# first_node_v2.net
KiCad netlist of a schematic drawn in EAGLE
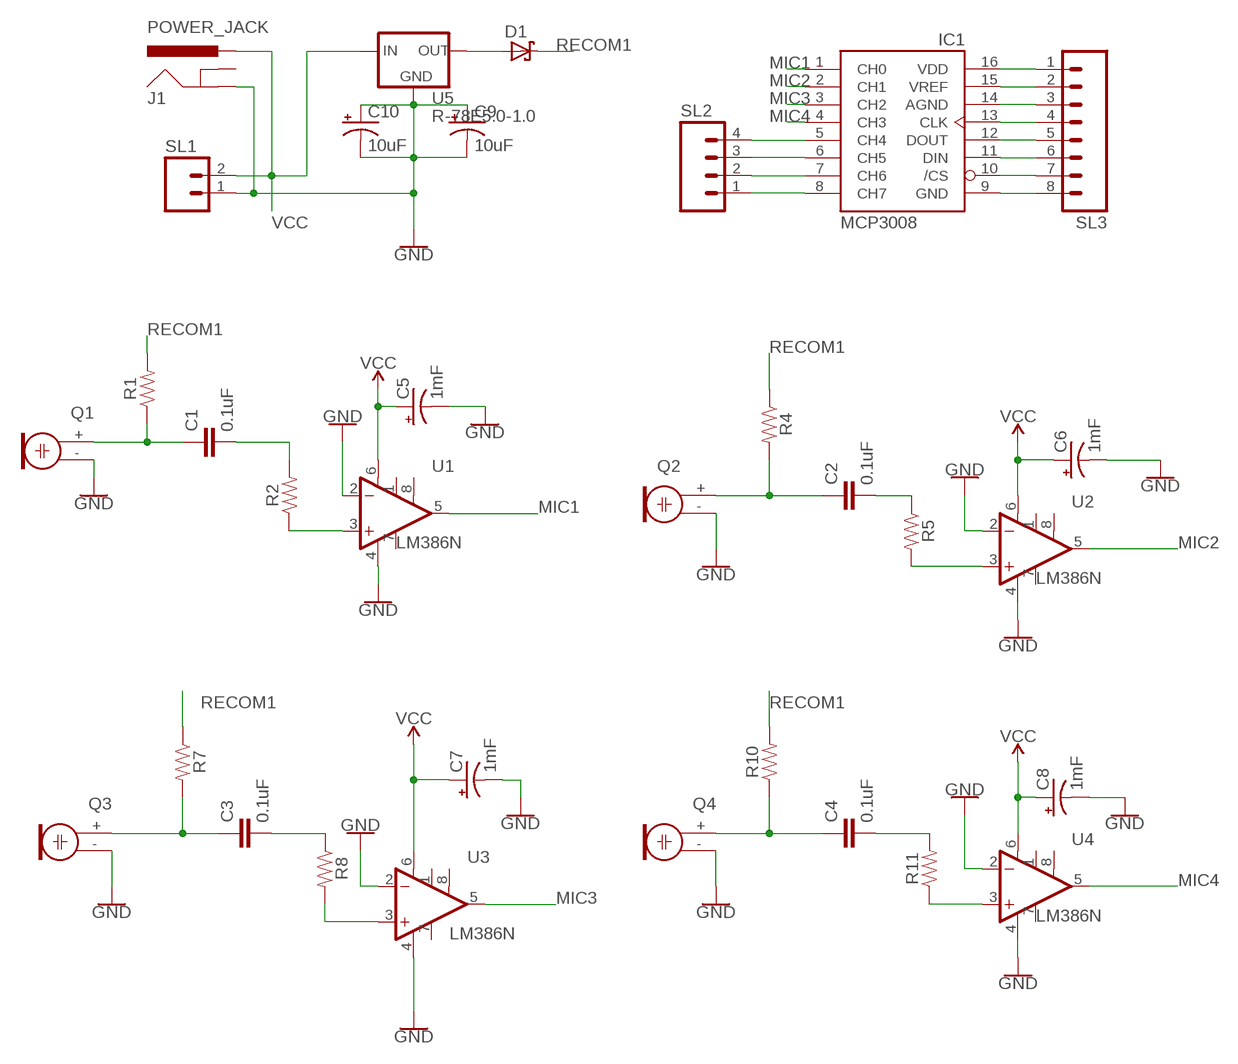
[diagram p0: schematic, sheet 1]

(export (version "E")
  (design (tool "Eeschema 10.0.6"))
  (components
    (comp (ref "C1")
      (value "0.1uF")
      (footprint "eagle-import:CAP-PTH-SMALL-KIT")
      (libsource (lib "eagle-import") (part "0.1UF-KIT-EZ-50V-20%"))
    )
    (comp (ref "C2")
      (value "0.1uF")
      (footprint "eagle-import:CAP-PTH-SMALL-KIT")
      (libsource (lib "eagle-import") (part "0.1UF-KIT-EZ-50V-20%"))
    )
    (comp (ref "C3")
      (value "0.1uF")
      (footprint "eagle-import:CAP-PTH-SMALL-KIT")
      (libsource (lib "eagle-import") (part "0.1UF-KIT-EZ-50V-20%"))
    )
    (comp (ref "C4")
      (value "0.1uF")
      (footprint "eagle-import:CAP-PTH-SMALL-KIT")
      (libsource (lib "eagle-import") (part "0.1UF-KIT-EZ-50V-20%"))
    )
    (comp (ref "C5")
      (value "1mF")
      (footprint "eagle-import:CPOL-RADIAL-5MM-10MM")
      (libsource (lib "eagle-import") (part "1000UF-RADIAL-5MM-25V-20%"))
    )
    (comp (ref "C6")
      (value "1mF")
      (footprint "eagle-import:CPOL-RADIAL-5MM-10MM")
      (libsource (lib "eagle-import") (part "1000UF-RADIAL-5MM-25V-20%"))
    )
    (comp (ref "C7")
      (value "1mF")
      (footprint "eagle-import:CPOL-RADIAL-5MM-10MM")
      (libsource (lib "eagle-import") (part "1000UF-RADIAL-5MM-25V-20%"))
    )
    (comp (ref "C8")
      (value "1mF")
      (footprint "eagle-import:CPOL-RADIAL-5MM-10MM")
      (libsource (lib "eagle-import") (part "1000UF-RADIAL-5MM-25V-20%"))
    )
    (comp (ref "C9")
      (value "10uF")
      (footprint "eagle-import:CPOL-RADIAL-2.5MM-5MM")
      (libsource (lib "eagle-import") (part "10UF-POLAR-RADIAL-2.5MM-25V-20%"))
    )
    (comp (ref "C10")
      (value "10uF")
      (footprint "eagle-import:CPOL-RADIAL-2.5MM-5MM")
      (libsource (lib "eagle-import") (part "10UF-POLAR-RADIAL-2.5MM-25V-20%"))
    )
    (comp (ref "D1")
      (value "SCHOTTKY-DIODECB429-17")
      (footprint "eagle-import:CB429-17")
      (libsource (lib "eagle-import") (part "SCHOTTKY-DIODECB429-17"))
    )
    (comp (ref "IC1")
      (value "MCP3008")
      (footprint "eagle-import:DIL16")
      (libsource (lib "eagle-import") (part "MCP3008"))
    )
    (comp (ref "J1")
      (value "POWER_JACK")
      (footprint "eagle-import:POWER_JACK_PTH")
      (libsource (lib "eagle-import") (part "POWER_JACK"))
    )
    (comp (ref "Q1")
      (value "ELECTRET")
      (footprint "eagle-import:9.7ELECTRET")
      (libsource (lib "eagle-import") (part "ELECTRET"))
    )
    (comp (ref "Q2")
      (value "ELECTRET")
      (footprint "eagle-import:9.7ELECTRET")
      (libsource (lib "eagle-import") (part "ELECTRET"))
    )
    (comp (ref "Q3")
      (value "ELECTRET")
      (footprint "eagle-import:9.7ELECTRET")
      (libsource (lib "eagle-import") (part "ELECTRET"))
    )
    (comp (ref "Q4")
      (value "ELECTRET")
      (footprint "eagle-import:9.7ELECTRET")
      (libsource (lib "eagle-import") (part "ELECTRET"))
    )
    (comp (ref "R1")
      (value "RESISTORAXIAL-0.3")
      (footprint "eagle-import:AXIAL-0.3")
      (libsource (lib "eagle-import") (part "RESISTORAXIAL-0.3"))
    )
    (comp (ref "R2")
      (value "RESISTORAXIAL-0.3")
      (footprint "eagle-import:AXIAL-0.3")
      (libsource (lib "eagle-import") (part "RESISTORAXIAL-0.3"))
    )
    (comp (ref "R4")
      (value "RESISTORAXIAL-0.3")
      (footprint "eagle-import:AXIAL-0.3")
      (libsource (lib "eagle-import") (part "RESISTORAXIAL-0.3"))
    )
    (comp (ref "R5")
      (value "RESISTORAXIAL-0.3")
      (footprint "eagle-import:AXIAL-0.3")
      (libsource (lib "eagle-import") (part "RESISTORAXIAL-0.3"))
    )
    (comp (ref "R7")
      (value "RESISTORAXIAL-0.3")
      (footprint "eagle-import:AXIAL-0.3")
      (libsource (lib "eagle-import") (part "RESISTORAXIAL-0.3"))
    )
    (comp (ref "R8")
      (value "RESISTORAXIAL-0.3")
      (footprint "eagle-import:AXIAL-0.3")
      (libsource (lib "eagle-import") (part "RESISTORAXIAL-0.3"))
    )
    (comp (ref "R10")
      (value "RESISTORAXIAL-0.3")
      (footprint "eagle-import:AXIAL-0.3")
      (libsource (lib "eagle-import") (part "RESISTORAXIAL-0.3"))
    )
    (comp (ref "R11")
      (value "RESISTORAXIAL-0.3")
      (footprint "eagle-import:AXIAL-0.3")
      (libsource (lib "eagle-import") (part "RESISTORAXIAL-0.3"))
    )
    (comp (ref "SL1")
      (value "M02")
      (footprint "eagle-import:02P")
      (libsource (lib "eagle-import") (part "M02"))
    )
    (comp (ref "SL2")
      (value "M04")
      (footprint "eagle-import:04P")
      (libsource (lib "eagle-import") (part "M04"))
    )
    (comp (ref "SL3")
      (value "M08")
      (footprint "eagle-import:08P")
      (libsource (lib "eagle-import") (part "M08"))
    )
    (comp (ref "U1")
      (value "LM386N")
      (footprint "eagle-import:DIP08")
      (libsource (lib "eagle-import") (part "LM386"))
    )
    (comp (ref "U2")
      (value "LM386N")
      (footprint "eagle-import:DIP08")
      (libsource (lib "eagle-import") (part "LM386"))
    )
    (comp (ref "U3")
      (value "LM386N")
      (footprint "eagle-import:DIP08")
      (libsource (lib "eagle-import") (part "LM386"))
    )
    (comp (ref "U4")
      (value "LM386N")
      (footprint "eagle-import:DIP08")
      (libsource (lib "eagle-import") (part "LM386"))
    )
    (comp (ref "U5")
      (value "R-78E5.0-1.0")
      (footprint "eagle-import:DC-DC_CONVERTER_78XX")
      (libsource (lib "eagle-import") (part "R-78E5.0-1.0"))
    )
  )
  (nets
    (net (code "1") (name "/MIC1") (class "Default")
      (node (ref "IC1") (pin "1") (pinfunction "CH0_1") (pintype "input"))
      (node (ref "U1") (pin "5") (pinfunction "OUT_5") (pintype "output"))
    )
    (net (code "2") (name "/MIC2") (class "Default")
      (node (ref "IC1") (pin "2") (pinfunction "CH1_2") (pintype "input"))
      (node (ref "U2") (pin "5") (pinfunction "OUT_5") (pintype "output"))
    )
    (net (code "3") (name "/MIC3") (class "Default")
      (node (ref "IC1") (pin "3") (pinfunction "CH2_3") (pintype "input"))
      (node (ref "U3") (pin "5") (pinfunction "OUT_5") (pintype "output"))
    )
    (net (code "4") (name "/MIC4") (class "Default")
      (node (ref "IC1") (pin "4") (pinfunction "CH3_4") (pintype "input"))
      (node (ref "U4") (pin "5") (pinfunction "OUT_5") (pintype "output"))
    )
    (net (code "5") (name "/RECOM1") (class "Default")
      (node (ref "D1") (pin "C") (pinfunction "C_C") (pintype "passive"))
      (node (ref "R1") (pin "P$2") (pinfunction "2_P$2") (pintype "passive"))
      (node (ref "R10") (pin "P$2") (pinfunction "2_P$2") (pintype "passive"))
      (node (ref "R4") (pin "P$1") (pinfunction "1_P$1") (pintype "passive"))
      (node (ref "R7") (pin "P$1") (pinfunction "1_P$1") (pintype "passive"))
    )
    (net (code "6") (name "GND") (class "Default")
      (node (ref "C10") (pin "1") (pinfunction "+_1") (pintype "passive"))
      (node (ref "C10") (pin "2") (pinfunction "-_2") (pintype "passive"))
      (node (ref "C5") (pin "-") (pinfunction "-_-") (pintype "passive"))
      (node (ref "C6") (pin "-") (pinfunction "-_-") (pintype "passive"))
      (node (ref "C7") (pin "-") (pinfunction "-_-") (pintype "passive"))
      (node (ref "C8") (pin "-") (pinfunction "-_-") (pintype "passive"))
      (node (ref "C9") (pin "1") (pinfunction "+_1") (pintype "passive"))
      (node (ref "C9") (pin "2") (pinfunction "-_2") (pintype "passive"))
      (node (ref "J1") (pin "GND") (pinfunction "GND_GND") (pintype "bidirectional"))
      (node (ref "Q1") (pin "-") (pinfunction "1_-") (pintype "passive"))
      (node (ref "Q2") (pin "-") (pinfunction "1_-") (pintype "passive"))
      (node (ref "Q3") (pin "-") (pinfunction "1_-") (pintype "passive"))
      (node (ref "Q4") (pin "-") (pinfunction "1_-") (pintype "passive"))
      (node (ref "SL1") (pin "1") (pinfunction "1_1") (pintype "passive"))
      (node (ref "U1") (pin "2") (pinfunction "-IN_2") (pintype "input"))
      (node (ref "U1") (pin "4") (pinfunction "V-_4") (pintype "power_in"))
      (node (ref "U2") (pin "2") (pinfunction "-IN_2") (pintype "input"))
      (node (ref "U2") (pin "4") (pinfunction "V-_4") (pintype "power_in"))
      (node (ref "U3") (pin "2") (pinfunction "-IN_2") (pintype "input"))
      (node (ref "U3") (pin "4") (pinfunction "V-_4") (pintype "power_in"))
      (node (ref "U4") (pin "2") (pinfunction "-IN_2") (pintype "input"))
      (node (ref "U4") (pin "4") (pinfunction "V-_4") (pintype "power_in"))
      (node (ref "U5") (pin "GND") (pinfunction "GND_GND") (pintype "input"))
    )
    (net (code "7") (name "Net-(IC1-AGND)") (class "Default")
      (node (ref "IC1") (pin "14") (pinfunction "AGND_14") (pintype "power_in"))
      (node (ref "SL3") (pin "3") (pinfunction "3_3") (pintype "passive"))
    )
    (net (code "8") (name "Net-(IC1-CH4)") (class "Default")
      (node (ref "IC1") (pin "5") (pinfunction "CH4_5") (pintype "input"))
      (node (ref "SL2") (pin "4") (pinfunction "4_4") (pintype "passive"))
    )
    (net (code "9") (name "Net-(IC1-CH5)") (class "Default")
      (node (ref "IC1") (pin "6") (pinfunction "CH5_6") (pintype "input"))
      (node (ref "SL2") (pin "3") (pinfunction "3_3") (pintype "passive"))
    )
    (net (code "10") (name "Net-(IC1-CH6)") (class "Default")
      (node (ref "IC1") (pin "7") (pinfunction "CH6_7") (pintype "input"))
      (node (ref "SL2") (pin "2") (pinfunction "2_2") (pintype "passive"))
    )
    (net (code "11") (name "Net-(IC1-CH7)") (class "Default")
      (node (ref "IC1") (pin "8") (pinfunction "CH7_8") (pintype "input"))
      (node (ref "SL2") (pin "1") (pinfunction "1_1") (pintype "passive"))
    )
    (net (code "12") (name "Net-(IC1-CLK)") (class "Default")
      (node (ref "IC1") (pin "13") (pinfunction "CLK_13") (pintype "input"))
      (node (ref "SL3") (pin "4") (pinfunction "4_4") (pintype "passive"))
    )
    (net (code "13") (name "Net-(IC1-DIN)") (class "Default")
      (node (ref "IC1") (pin "11") (pinfunction "DIN_11") (pintype "input"))
      (node (ref "SL3") (pin "6") (pinfunction "6_6") (pintype "passive"))
    )
    (net (code "14") (name "Net-(IC1-DOUT)") (class "Default")
      (node (ref "IC1") (pin "12") (pinfunction "DOUT_12") (pintype "output"))
      (node (ref "SL3") (pin "5") (pinfunction "5_5") (pintype "passive"))
    )
    (net (code "15") (name "Net-(IC1-GND)") (class "Default")
      (node (ref "IC1") (pin "9") (pinfunction "GND_9") (pintype "power_in"))
      (node (ref "SL3") (pin "8") (pinfunction "8_8") (pintype "passive"))
    )
    (net (code "16") (name "Net-(IC1-VDD)") (class "Default")
      (node (ref "IC1") (pin "16") (pinfunction "VDD_16") (pintype "power_in"))
      (node (ref "SL3") (pin "1") (pinfunction "1_1") (pintype "passive"))
    )
    (net (code "17") (name "Net-(IC1-VREF)") (class "Default")
      (node (ref "IC1") (pin "15") (pinfunction "VREF_15") (pintype "input"))
      (node (ref "SL3") (pin "2") (pinfunction "2_2") (pintype "passive"))
    )
    (net (code "18") (name "Net-(IC1-{slash}CS)") (class "Default")
      (node (ref "IC1") (pin "10") (pinfunction "/CS_10") (pintype "input"))
      (node (ref "SL3") (pin "7") (pinfunction "7_7") (pintype "passive"))
    )
    (net (code "19") (name "Net-(Q1-2)") (class "Default")
      (node (ref "C1") (pin "1") (pinfunction "1_1") (pintype "passive"))
      (node (ref "Q1") (pin "+") (pinfunction "2_+") (pintype "passive"))
      (node (ref "R1") (pin "P$1") (pinfunction "1_P$1") (pintype "passive"))
    )
    (net (code "20") (name "Net-(Q2-2)") (class "Default")
      (node (ref "C2") (pin "1") (pinfunction "1_1") (pintype "passive"))
      (node (ref "Q2") (pin "+") (pinfunction "2_+") (pintype "passive"))
      (node (ref "R4") (pin "P$2") (pinfunction "2_P$2") (pintype "passive"))
    )
    (net (code "21") (name "Net-(Q3-2)") (class "Default")
      (node (ref "C3") (pin "1") (pinfunction "1_1") (pintype "passive"))
      (node (ref "Q3") (pin "+") (pinfunction "2_+") (pintype "passive"))
      (node (ref "R7") (pin "P$2") (pinfunction "2_P$2") (pintype "passive"))
    )
    (net (code "22") (name "Net-(Q4-2)") (class "Default")
      (node (ref "C4") (pin "1") (pinfunction "1_1") (pintype "passive"))
      (node (ref "Q4") (pin "+") (pinfunction "2_+") (pintype "passive"))
      (node (ref "R10") (pin "P$1") (pinfunction "1_P$1") (pintype "passive"))
    )
    (net (code "23") (name "Net-(R2-1)") (class "Default")
      (node (ref "R2") (pin "P$1") (pinfunction "1_P$1") (pintype "passive"))
      (node (ref "U1") (pin "3") (pinfunction "+IN_3") (pintype "input"))
    )
    (net (code "24") (name "Net-(R2-2)") (class "Default")
      (node (ref "C1") (pin "2") (pinfunction "2_2") (pintype "passive"))
      (node (ref "R2") (pin "P$2") (pinfunction "2_P$2") (pintype "passive"))
    )
    (net (code "25") (name "Net-(R5-1)") (class "Default")
      (node (ref "C2") (pin "2") (pinfunction "2_2") (pintype "passive"))
      (node (ref "R5") (pin "P$1") (pinfunction "1_P$1") (pintype "passive"))
    )
    (net (code "26") (name "Net-(R5-2)") (class "Default")
      (node (ref "R5") (pin "P$2") (pinfunction "2_P$2") (pintype "passive"))
      (node (ref "U2") (pin "3") (pinfunction "+IN_3") (pintype "input"))
    )
    (net (code "27") (name "Net-(R8-1)") (class "Default")
      (node (ref "C3") (pin "2") (pinfunction "2_2") (pintype "passive"))
      (node (ref "R8") (pin "P$1") (pinfunction "1_P$1") (pintype "passive"))
    )
    (net (code "28") (name "Net-(R8-2)") (class "Default")
      (node (ref "R8") (pin "P$2") (pinfunction "2_P$2") (pintype "passive"))
      (node (ref "U3") (pin "3") (pinfunction "+IN_3") (pintype "input"))
    )
    (net (code "29") (name "Net-(R11-1)") (class "Default")
      (node (ref "R11") (pin "P$1") (pinfunction "1_P$1") (pintype "passive"))
      (node (ref "U4") (pin "3") (pinfunction "+IN_3") (pintype "input"))
    )
    (net (code "30") (name "Net-(R11-2)") (class "Default")
      (node (ref "C4") (pin "2") (pinfunction "2_2") (pintype "passive"))
      (node (ref "R11") (pin "P$2") (pinfunction "2_P$2") (pintype "passive"))
    )
    (net (code "31") (name "Net-(U5-OUT)") (class "Default")
      (node (ref "D1") (pin "A") (pinfunction "A_A") (pintype "passive"))
      (node (ref "U5") (pin "VOUT") (pinfunction "OUT_VOUT") (pintype "passive"))
    )
    (net (code "32") (name "VCC") (class "Default")
      (node (ref "C5") (pin "+") (pinfunction "+_+") (pintype "passive"))
      (node (ref "C6") (pin "+") (pinfunction "+_+") (pintype "passive"))
      (node (ref "C7") (pin "+") (pinfunction "+_+") (pintype "passive"))
      (node (ref "C8") (pin "+") (pinfunction "+_+") (pintype "passive"))
      (node (ref "J1") (pin "PWR") (pinfunction "PWR_PWR") (pintype "bidirectional"))
      (node (ref "SL1") (pin "2") (pinfunction "2_2") (pintype "passive"))
      (node (ref "U1") (pin "6") (pinfunction "V+_6") (pintype "power_in"))
      (node (ref "U2") (pin "6") (pinfunction "V+_6") (pintype "power_in"))
      (node (ref "U3") (pin "6") (pinfunction "V+_6") (pintype "power_in"))
      (node (ref "U4") (pin "6") (pinfunction "V+_6") (pintype "power_in"))
      (node (ref "U5") (pin "VIN") (pinfunction "IN_VIN") (pintype "input"))
    )
    (net (code "33") (name "unconnected-(J1-PadGNDBREAK)") (class "Default")
      (node (ref "J1") (pin "GNDBREAK") (pinfunction "GNDBREAK_GNDBREAK") (pintype "bidirectional"))
    )
    (net (code "34") (name "unconnected-(U1-BP-Pad7)") (class "Default")
      (node (ref "U1") (pin "7") (pinfunction "BP_7") (pintype "bidirectional"))
    )
    (net (code "35") (name "unconnected-(U1-GAIN-Pad1)") (class "Default")
      (node (ref "U1") (pin "1") (pinfunction "GAIN_1") (pintype "bidirectional"))
    )
    (net (code "36") (name "unconnected-(U1-GAIN-Pad8)") (class "Default")
      (node (ref "U1") (pin "8") (pinfunction "GAIN_8") (pintype "bidirectional"))
    )
    (net (code "37") (name "unconnected-(U2-BP-Pad7)") (class "Default")
      (node (ref "U2") (pin "7") (pinfunction "BP_7") (pintype "bidirectional"))
    )
    (net (code "38") (name "unconnected-(U2-GAIN-Pad1)") (class "Default")
      (node (ref "U2") (pin "1") (pinfunction "GAIN_1") (pintype "bidirectional"))
    )
    (net (code "39") (name "unconnected-(U2-GAIN-Pad8)") (class "Default")
      (node (ref "U2") (pin "8") (pinfunction "GAIN_8") (pintype "bidirectional"))
    )
    (net (code "40") (name "unconnected-(U3-BP-Pad7)") (class "Default")
      (node (ref "U3") (pin "7") (pinfunction "BP_7") (pintype "bidirectional"))
    )
    (net (code "41") (name "unconnected-(U3-GAIN-Pad1)") (class "Default")
      (node (ref "U3") (pin "1") (pinfunction "GAIN_1") (pintype "bidirectional"))
    )
    (net (code "42") (name "unconnected-(U3-GAIN-Pad8)") (class "Default")
      (node (ref "U3") (pin "8") (pinfunction "GAIN_8") (pintype "bidirectional"))
    )
    (net (code "43") (name "unconnected-(U4-BP-Pad7)") (class "Default")
      (node (ref "U4") (pin "7") (pinfunction "BP_7") (pintype "bidirectional"))
    )
    (net (code "44") (name "unconnected-(U4-GAIN-Pad1)") (class "Default")
      (node (ref "U4") (pin "1") (pinfunction "GAIN_1") (pintype "bidirectional"))
    )
    (net (code "45") (name "unconnected-(U4-GAIN-Pad8)") (class "Default")
      (node (ref "U4") (pin "8") (pinfunction "GAIN_8") (pintype "bidirectional"))
    )
  )
)
